# controller.net
KiCad netlist of a schematic drawn in EAGLE
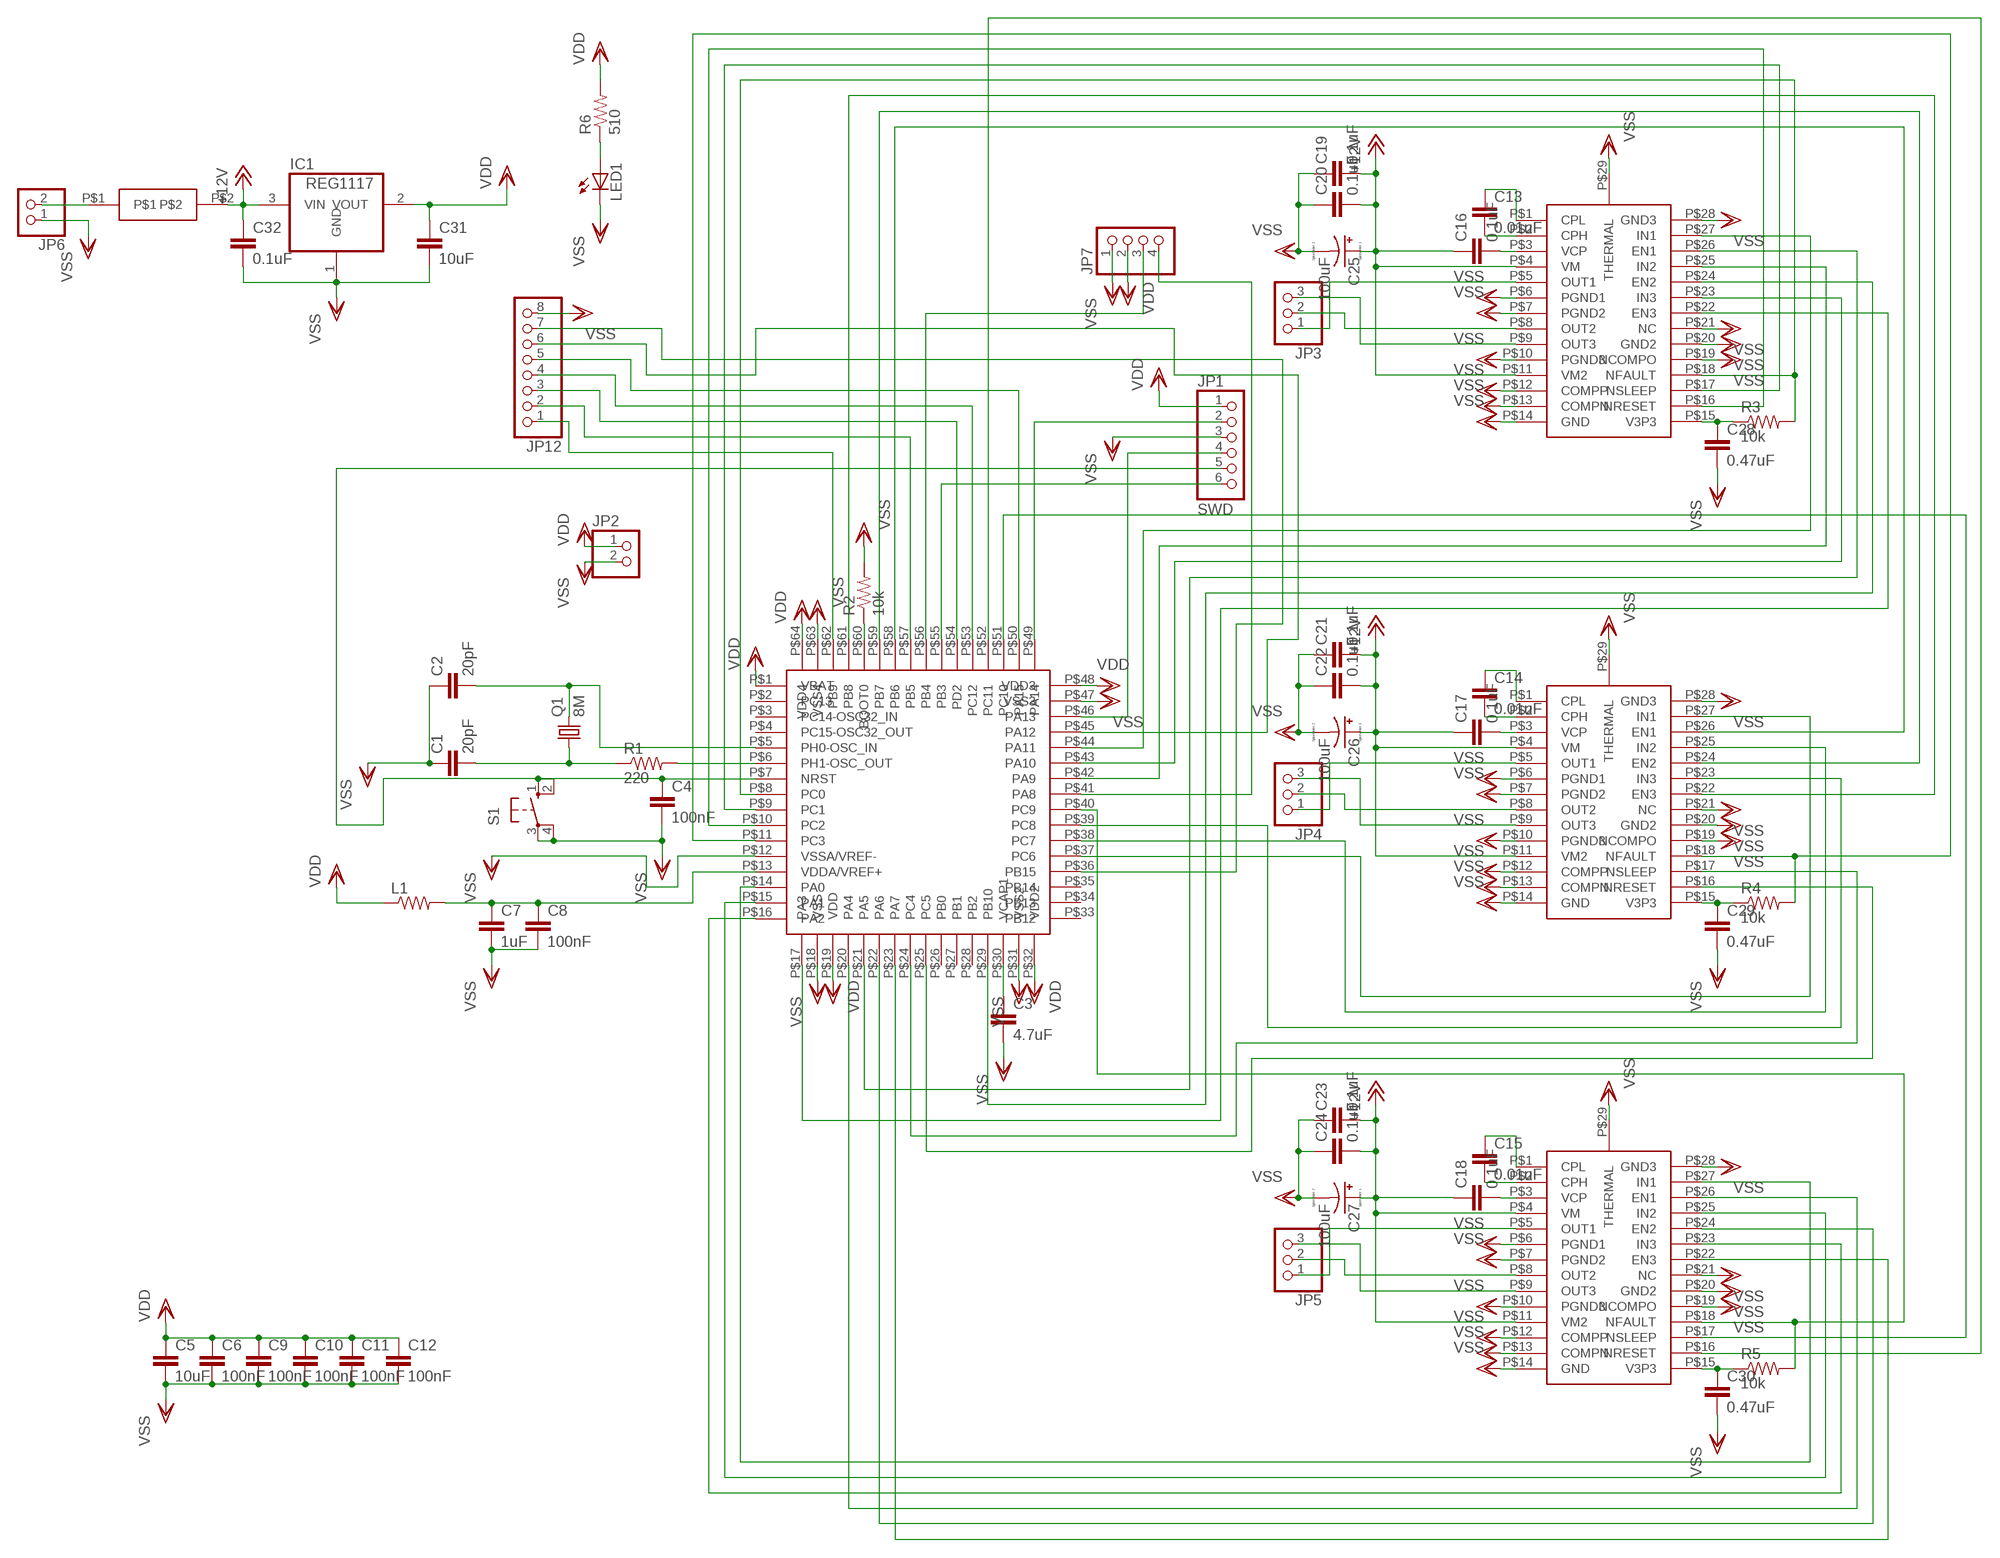
[diagram p0: schematic, sheet 1]

(export (version "E")
  (design (tool "Eeschema 10.0.6"))
  (components
    (comp (ref "C1")
      (value "20pF")
      (footprint "eagle-import:C0402")
      (libsource (lib "eagle-import") (part "C-EUC0402"))
    )
    (comp (ref "C2")
      (value "20pF")
      (footprint "eagle-import:C0402")
      (libsource (lib "eagle-import") (part "C-EUC0402"))
    )
    (comp (ref "C3")
      (value "4.7uF")
      (footprint "eagle-import:C1206")
      (libsource (lib "eagle-import") (part "C-EUC1206"))
    )
    (comp (ref "C4")
      (value "100nF")
      (footprint "eagle-import:C0402")
      (libsource (lib "eagle-import") (part "C-EUC0402"))
    )
    (comp (ref "C5")
      (value "10uF")
      (footprint "eagle-import:C1206")
      (libsource (lib "eagle-import") (part "C-EUC1206"))
    )
    (comp (ref "C6")
      (value "100nF")
      (footprint "eagle-import:C0402")
      (libsource (lib "eagle-import") (part "C-EUC0402"))
    )
    (comp (ref "C7")
      (value "1uF")
      (footprint "eagle-import:C0603")
      (libsource (lib "eagle-import") (part "C-EUC0603"))
    )
    (comp (ref "C8")
      (value "100nF")
      (footprint "eagle-import:C0402")
      (libsource (lib "eagle-import") (part "C-EUC0402"))
    )
    (comp (ref "C9")
      (value "100nF")
      (footprint "eagle-import:C0402")
      (libsource (lib "eagle-import") (part "C-EUC0402"))
    )
    (comp (ref "C10")
      (value "100nF")
      (footprint "eagle-import:C0402")
      (libsource (lib "eagle-import") (part "C-EUC0402"))
    )
    (comp (ref "C11")
      (value "100nF")
      (footprint "eagle-import:C0402")
      (libsource (lib "eagle-import") (part "C-EUC0402"))
    )
    (comp (ref "C12")
      (value "100nF")
      (footprint "eagle-import:C0402")
      (libsource (lib "eagle-import") (part "C-EUC0402"))
    )
    (comp (ref "C13")
      (value "0.01uF")
      (footprint "eagle-import:C0603")
      (libsource (lib "eagle-import") (part "C-EUC0603"))
    )
    (comp (ref "C14")
      (value "0.01uF")
      (footprint "eagle-import:C0603")
      (libsource (lib "eagle-import") (part "C-EUC0603"))
    )
    (comp (ref "C15")
      (value "0.01uF")
      (footprint "eagle-import:C0603")
      (libsource (lib "eagle-import") (part "C-EUC0603"))
    )
    (comp (ref "C16")
      (value "0.1uF")
      (footprint "eagle-import:C0603")
      (libsource (lib "eagle-import") (part "C-EUC0603"))
    )
    (comp (ref "C17")
      (value "0.1uF")
      (footprint "eagle-import:C0603")
      (libsource (lib "eagle-import") (part "C-EUC0603"))
    )
    (comp (ref "C18")
      (value "0.1uF")
      (footprint "eagle-import:C0603")
      (libsource (lib "eagle-import") (part "C-EUC0603"))
    )
    (comp (ref "C19")
      (value "0.1uF")
      (footprint "eagle-import:C0603")
      (libsource (lib "eagle-import") (part "C-EUC0603"))
    )
    (comp (ref "C20")
      (value "0.1uF")
      (footprint "eagle-import:C0603")
      (libsource (lib "eagle-import") (part "C-EUC0603"))
    )
    (comp (ref "C21")
      (value "0.1uF")
      (footprint "eagle-import:C0603")
      (libsource (lib "eagle-import") (part "C-EUC0603"))
    )
    (comp (ref "C22")
      (value "0.1uF")
      (footprint "eagle-import:C0603")
      (libsource (lib "eagle-import") (part "C-EUC0603"))
    )
    (comp (ref "C23")
      (value "0.1uF")
      (footprint "eagle-import:C0603")
      (libsource (lib "eagle-import") (part "C-EUC0603"))
    )
    (comp (ref "C24")
      (value "0.1uF")
      (footprint "eagle-import:C0603")
      (libsource (lib "eagle-import") (part "C-EUC0603"))
    )
    (comp (ref "C25")
      (value "100uF")
      (footprint "eagle-import:PANASONIC_D")
      (libsource (lib "eagle-import") (part "CPOL-USD"))
    )
    (comp (ref "C26")
      (value "100uF")
      (footprint "eagle-import:PANASONIC_D")
      (libsource (lib "eagle-import") (part "CPOL-USD"))
    )
    (comp (ref "C27")
      (value "100uF")
      (footprint "eagle-import:PANASONIC_D")
      (libsource (lib "eagle-import") (part "CPOL-USD"))
    )
    (comp (ref "C28")
      (value "0.47uF")
      (footprint "eagle-import:C0603")
      (libsource (lib "eagle-import") (part "C-EUC0603"))
    )
    (comp (ref "C29")
      (value "0.47uF")
      (footprint "eagle-import:C0603")
      (libsource (lib "eagle-import") (part "C-EUC0603"))
    )
    (comp (ref "C30")
      (value "0.47uF")
      (footprint "eagle-import:C0603")
      (libsource (lib "eagle-import") (part "C-EUC0603"))
    )
    (comp (ref "C31")
      (value "10uF")
      (footprint "eagle-import:C1206")
      (libsource (lib "eagle-import") (part "C-EUC1206"))
    )
    (comp (ref "C32")
      (value "0.1uF")
      (footprint "eagle-import:C1206")
      (libsource (lib "eagle-import") (part "C-EUC1206"))
    )
    (comp (ref "IC1")
      (value "REG1117")
      (footprint "eagle-import:SOT223")
      (libsource (lib "eagle-import") (part "REG1117"))
    )
    (comp (ref "JP1")
      (value "SWD")
      (footprint "eagle-import:1X06")
      (libsource (lib "eagle-import") (part "PINHD-1X6"))
    )
    (comp (ref "JP2")
      (value "PINHD-1X2")
      (footprint "eagle-import:1X02")
      (libsource (lib "eagle-import") (part "PINHD-1X2"))
    )
    (comp (ref "JP3")
      (value "PINHD-1X3")
      (footprint "eagle-import:1X03")
      (libsource (lib "eagle-import") (part "PINHD-1X3"))
    )
    (comp (ref "JP4")
      (value "PINHD-1X3")
      (footprint "eagle-import:1X03")
      (libsource (lib "eagle-import") (part "PINHD-1X3"))
    )
    (comp (ref "JP5")
      (value "PINHD-1X3")
      (footprint "eagle-import:1X03")
      (libsource (lib "eagle-import") (part "PINHD-1X3"))
    )
    (comp (ref "JP6")
      (value "PINHD-1X2")
      (footprint "eagle-import:1X02")
      (libsource (lib "eagle-import") (part "PINHD-1X2"))
    )
    (comp (ref "JP7")
      (value "PINHD-1X4")
      (footprint "eagle-import:1X04")
      (libsource (lib "eagle-import") (part "PINHD-1X4"))
    )
    (comp (ref "JP12")
      (value "PINHD-1X8")
      (footprint "eagle-import:1X08")
      (libsource (lib "eagle-import") (part "PINHD-1X8"))
    )
    (comp (ref "L1")
      (value "R-US_R0603")
      (footprint "eagle-import:R0603")
      (libsource (lib "eagle-import") (part "R-US_R0603"))
    )
    (comp (ref "LED1")
      (value "LEDCHIP-LED0603")
      (footprint "eagle-import:CHIP-LED0603")
      (libsource (lib "eagle-import") (part "LEDCHIP-LED0603"))
    )
    (comp (ref "Q1")
      (value "8M")
      (footprint "eagle-import:HC49_S")
      (libsource (lib "eagle-import") (part "CRYSTALHC49S"))
    )
    (comp (ref "R1")
      (value "220")
      (footprint "eagle-import:R0402")
      (libsource (lib "eagle-import") (part "R-US_R0402"))
    )
    (comp (ref "R2")
      (value "10k")
      (footprint "eagle-import:R0402")
      (libsource (lib "eagle-import") (part "R-US_R0402"))
    )
    (comp (ref "R3")
      (value "10k")
      (footprint "eagle-import:R0402")
      (libsource (lib "eagle-import") (part "R-US_R0402"))
    )
    (comp (ref "R4")
      (value "10k")
      (footprint "eagle-import:R0402")
      (libsource (lib "eagle-import") (part "R-US_R0402"))
    )
    (comp (ref "R5")
      (value "10k")
      (footprint "eagle-import:R0402")
      (libsource (lib "eagle-import") (part "R-US_R0402"))
    )
    (comp (ref "R6")
      (value "510")
      (footprint "eagle-import:R0402")
      (libsource (lib "eagle-import") (part "R-US_R0402"))
    )
    (comp (ref "S1")
      (value "10-XX")
      (footprint "eagle-import:B3F-10XX")
      (fields (field (name "MPN") "B3F-1000"))
      (libsource (lib "eagle-import") (part "10-XX"))
    )
    (comp (ref "U$1")
      (value "STM32F411VET6")
      (footprint "eagle-import:STM32F411VET6")
      (libsource (lib "eagle-import") (part "STM32F411VET6"))
    )
    (comp (ref "U$2")
      (value "DRV8313")
      (footprint "eagle-import:DRV8313")
      (libsource (lib "eagle-import") (part "DRV8313"))
    )
    (comp (ref "U$3")
      (value "DRV8313")
      (footprint "eagle-import:DRV8313")
      (libsource (lib "eagle-import") (part "DRV8313"))
    )
    (comp (ref "U$4")
      (value "DRV8313")
      (footprint "eagle-import:DRV8313")
      (libsource (lib "eagle-import") (part "DRV8313"))
    )
    (comp (ref "U$5")
      (value "SOD123")
      (footprint "eagle-import:SOD123")
      (libsource (lib "eagle-import") (part "SOD123"))
    )
  )
  (nets
    (net (code "1") (name "+12V") (class "Default")
      (node (ref "C16") (pin "1") (pinfunction "1_1") (pintype "passive"))
      (node (ref "C17") (pin "1") (pinfunction "1_1") (pintype "passive"))
      (node (ref "C18") (pin "1") (pinfunction "1_1") (pintype "passive"))
      (node (ref "C19") (pin "2") (pinfunction "2_2") (pintype "passive"))
      (node (ref "C20") (pin "2") (pinfunction "2_2") (pintype "passive"))
      (node (ref "C21") (pin "2") (pinfunction "2_2") (pintype "passive"))
      (node (ref "C22") (pin "2") (pinfunction "2_2") (pintype "passive"))
      (node (ref "C23") (pin "2") (pinfunction "2_2") (pintype "passive"))
      (node (ref "C24") (pin "2") (pinfunction "2_2") (pintype "passive"))
      (node (ref "C25") (pin "+") (pinfunction "+_+") (pintype "passive"))
      (node (ref "C26") (pin "+") (pinfunction "+_+") (pintype "passive"))
      (node (ref "C27") (pin "+") (pinfunction "+_+") (pintype "passive"))
      (node (ref "C32") (pin "1") (pinfunction "1_1") (pintype "passive"))
      (node (ref "IC1") (pin "3") (pinfunction "VIN_3") (pintype "input"))
      (node (ref "U$2") (pin "P$11") (pinfunction "VM2_P$11") (pintype "bidirectional"))
      (node (ref "U$2") (pin "P$4") (pinfunction "VM_P$4") (pintype "bidirectional"))
      (node (ref "U$3") (pin "P$11") (pinfunction "VM2_P$11") (pintype "bidirectional"))
      (node (ref "U$3") (pin "P$4") (pinfunction "VM_P$4") (pintype "bidirectional"))
      (node (ref "U$4") (pin "P$11") (pinfunction "VM2_P$11") (pintype "bidirectional"))
      (node (ref "U$4") (pin "P$4") (pinfunction "VM_P$4") (pintype "bidirectional"))
      (node (ref "U$5") (pin "P$2") (pinfunction "P$2_P$2") (pintype "bidirectional"))
    )
    (net (code "2") (name "Net-(C1-Pad2)") (class "Default")
      (node (ref "C1") (pin "2") (pinfunction "2_2") (pintype "passive"))
      (node (ref "Q1") (pin "1") (pinfunction "1_1") (pintype "passive"))
      (node (ref "R1") (pin "1") (pinfunction "1_1") (pintype "passive"))
    )
    (net (code "3") (name "Net-(JP6-Pad2)") (class "Default")
      (node (ref "JP6") (pin "2") (pinfunction "2_2") (pintype "passive"))
      (node (ref "U$5") (pin "P$1") (pinfunction "P$1_P$1") (pintype "bidirectional"))
    )
    (net (code "4") (name "Net-(LED1-PadA)") (class "Default")
      (node (ref "LED1") (pin "A") (pinfunction "A_A") (pintype "passive"))
      (node (ref "R6") (pin "1") (pinfunction "1_1") (pintype "passive"))
    )
    (net (code "5") (name "Net-(S1-S)") (class "Default")
      (node (ref "C4") (pin "1") (pinfunction "1_1") (pintype "passive"))
      (node (ref "JP1") (pin "5") (pinfunction "5_5") (pintype "passive"))
      (node (ref "S1") (pin "1") (pinfunction "S_1") (pintype "passive"))
      (node (ref "S1") (pin "2") (pinfunction "S1_2") (pintype "passive"))
      (node (ref "U$1") (pin "P$7") (pinfunction "NRST_P$7") (pintype "bidirectional"))
    )
    (net (code "6") (name "Net-(U$1-BOOT0)") (class "Default")
      (node (ref "R2") (pin "1") (pinfunction "1_1") (pintype "passive"))
      (node (ref "U$1") (pin "P$60") (pinfunction "BOOT0_P$60") (pintype "bidirectional"))
    )
    (net (code "7") (name "Net-(U$1-PA0)") (class "Default")
      (node (ref "U$1") (pin "P$14") (pinfunction "PA0_P$14") (pintype "bidirectional"))
      (node (ref "U$4") (pin "P$27") (pinfunction "IN1_P$27") (pintype "bidirectional"))
    )
    (net (code "8") (name "Net-(U$1-PA1)") (class "Default")
      (node (ref "U$1") (pin "P$15") (pinfunction "PA1_P$15") (pintype "bidirectional"))
      (node (ref "U$4") (pin "P$25") (pinfunction "IN2_P$25") (pintype "bidirectional"))
    )
    (net (code "9") (name "Net-(U$1-PA2)") (class "Default")
      (node (ref "U$1") (pin "P$16") (pinfunction "PA2_P$16") (pintype "bidirectional"))
      (node (ref "U$4") (pin "P$23") (pinfunction "IN3_P$23") (pintype "bidirectional"))
    )
    (net (code "10") (name "Net-(U$1-PA3)") (class "Default")
      (node (ref "U$1") (pin "P$17") (pinfunction "PA3_P$17") (pintype "bidirectional"))
      (node (ref "U$2") (pin "P$22") (pinfunction "EN3_P$22") (pintype "bidirectional"))
    )
    (net (code "11") (name "Net-(U$1-PA4)") (class "Default")
      (node (ref "U$1") (pin "P$20") (pinfunction "PA4_P$20") (pintype "bidirectional"))
      (node (ref "U$4") (pin "P$26") (pinfunction "EN1_P$26") (pintype "bidirectional"))
    )
    (net (code "12") (name "Net-(U$1-PA5)") (class "Default")
      (node (ref "U$1") (pin "P$21") (pinfunction "PA5_P$21") (pintype "bidirectional"))
      (node (ref "U$2") (pin "P$26") (pinfunction "EN1_P$26") (pintype "bidirectional"))
    )
    (net (code "13") (name "Net-(U$1-PA6)") (class "Default")
      (node (ref "U$1") (pin "P$22") (pinfunction "PA6_P$22") (pintype "bidirectional"))
      (node (ref "U$4") (pin "P$24") (pinfunction "EN2_P$24") (pintype "bidirectional"))
    )
    (net (code "14") (name "Net-(U$1-PA7)") (class "Default")
      (node (ref "U$1") (pin "P$23") (pinfunction "PA7_P$23") (pintype "bidirectional"))
      (node (ref "U$4") (pin "P$22") (pinfunction "EN3_P$22") (pintype "bidirectional"))
    )
    (net (code "15") (name "Net-(U$1-PA8)") (class "Default")
      (node (ref "JP7") (pin "4") (pinfunction "4_4") (pintype "passive"))
      (node (ref "U$1") (pin "P$41") (pinfunction "PA8_P$41") (pintype "bidirectional"))
    )
    (net (code "16") (name "Net-(U$1-PA9)") (class "Default")
      (node (ref "U$1") (pin "P$42") (pinfunction "PA9_P$42") (pintype "bidirectional"))
      (node (ref "U$2") (pin "P$25") (pinfunction "IN2_P$25") (pintype "bidirectional"))
    )
    (net (code "17") (name "Net-(U$1-PA10)") (class "Default")
      (node (ref "U$1") (pin "P$43") (pinfunction "PA10_P$43") (pintype "bidirectional"))
      (node (ref "U$2") (pin "P$23") (pinfunction "IN3_P$23") (pintype "bidirectional"))
    )
    (net (code "18") (name "Net-(U$1-PA11)") (class "Default")
      (node (ref "U$1") (pin "P$44") (pinfunction "PA11_P$44") (pintype "bidirectional"))
      (node (ref "U$2") (pin "P$27") (pinfunction "IN1_P$27") (pintype "bidirectional"))
    )
    (net (code "19") (name "Net-(U$1-PA12)") (class "Default")
      (node (ref "JP12") (pin "6") (pinfunction "6_6") (pintype "passive"))
      (node (ref "U$1") (pin "P$45") (pinfunction "PA12_P$45") (pintype "bidirectional"))
    )
    (net (code "20") (name "Net-(U$1-PA13)") (class "Default")
      (node (ref "JP1") (pin "4") (pinfunction "4_4") (pintype "passive"))
      (node (ref "U$1") (pin "P$46") (pinfunction "PA13_P$46") (pintype "bidirectional"))
    )
    (net (code "21") (name "Net-(U$1-PA14)") (class "Default")
      (node (ref "JP1") (pin "2") (pinfunction "2_2") (pintype "passive"))
      (node (ref "U$1") (pin "P$49") (pinfunction "PA14_P$49") (pintype "bidirectional"))
    )
    (net (code "22") (name "Net-(U$1-PA15)") (class "Default")
      (node (ref "JP12") (pin "5") (pinfunction "5_5") (pintype "passive"))
      (node (ref "U$1") (pin "P$50") (pinfunction "PA15_P$50") (pintype "bidirectional"))
    )
    (net (code "23") (name "Net-(U$1-PB3)") (class "Default")
      (node (ref "JP1") (pin "6") (pinfunction "6_6") (pintype "passive"))
      (node (ref "U$1") (pin "P$55") (pinfunction "PB3_P$55") (pintype "bidirectional"))
    )
    (net (code "24") (name "Net-(U$1-PB4)") (class "Default")
      (node (ref "JP7") (pin "3") (pinfunction "3_3") (pintype "passive"))
      (node (ref "U$1") (pin "P$56") (pinfunction "PB4_P$56") (pintype "bidirectional"))
    )
    (net (code "25") (name "Net-(U$1-PB5)") (class "Default")
      (node (ref "JP12") (pin "2") (pinfunction "2_2") (pintype "passive"))
      (node (ref "U$1") (pin "P$57") (pinfunction "PB5_P$57") (pintype "bidirectional"))
    )
    (net (code "26") (name "Net-(U$1-PB6)") (class "Default")
      (node (ref "U$1") (pin "P$58") (pinfunction "PB6_P$58") (pintype "bidirectional"))
      (node (ref "U$3") (pin "P$26") (pinfunction "EN1_P$26") (pintype "bidirectional"))
    )
    (net (code "27") (name "Net-(U$1-PB7)") (class "Default")
      (node (ref "U$1") (pin "P$59") (pinfunction "PB7_P$59") (pintype "bidirectional"))
      (node (ref "U$3") (pin "P$24") (pinfunction "EN2_P$24") (pintype "bidirectional"))
    )
    (net (code "28") (name "Net-(U$1-PB8)") (class "Default")
      (node (ref "U$1") (pin "P$61") (pinfunction "PB8_P$61") (pintype "bidirectional"))
      (node (ref "U$3") (pin "P$22") (pinfunction "EN3_P$22") (pintype "bidirectional"))
    )
    (net (code "29") (name "Net-(U$1-PB9)") (class "Default")
      (node (ref "JP12") (pin "1") (pinfunction "1_1") (pintype "passive"))
      (node (ref "U$1") (pin "P$62") (pinfunction "PB9_P$62") (pintype "bidirectional"))
    )
    (net (code "30") (name "Net-(U$1-PB10)") (class "Default")
      (node (ref "U$1") (pin "P$29") (pinfunction "PB10_P$29") (pintype "bidirectional"))
      (node (ref "U$2") (pin "P$24") (pinfunction "EN2_P$24") (pintype "bidirectional"))
    )
    (net (code "31") (name "Net-(U$1-PB15)") (class "Default")
      (node (ref "JP12") (pin "7") (pinfunction "7_7") (pintype "passive"))
      (node (ref "U$1") (pin "P$36") (pinfunction "PB15_P$36") (pintype "bidirectional"))
    )
    (net (code "32") (name "Net-(U$1-PC0)") (class "Default")
      (node (ref "R3") (pin "2") (pinfunction "2_2") (pintype "passive"))
      (node (ref "U$1") (pin "P$8") (pinfunction "PC0_P$8") (pintype "bidirectional"))
      (node (ref "U$2") (pin "P$18") (pinfunction "NFAULT_P$18") (pintype "bidirectional"))
    )
    (net (code "33") (name "Net-(U$1-PC1)") (class "Default")
      (node (ref "U$1") (pin "P$9") (pinfunction "PC1_P$9") (pintype "bidirectional"))
      (node (ref "U$2") (pin "P$17") (pinfunction "NSLEEP_P$17") (pintype "bidirectional"))
    )
    (net (code "34") (name "Net-(U$1-PC2)") (class "Default")
      (node (ref "U$1") (pin "P$10") (pinfunction "PC2_P$10") (pintype "bidirectional"))
      (node (ref "U$2") (pin "P$16") (pinfunction "NRESET_P$16") (pintype "bidirectional"))
    )
    (net (code "35") (name "Net-(U$1-PC3)") (class "Default")
      (node (ref "R4") (pin "2") (pinfunction "2_2") (pintype "passive"))
      (node (ref "U$1") (pin "P$11") (pinfunction "PC3_P$11") (pintype "bidirectional"))
      (node (ref "U$3") (pin "P$18") (pinfunction "NFAULT_P$18") (pintype "bidirectional"))
    )
    (net (code "36") (name "Net-(U$1-PC4)") (class "Default")
      (node (ref "U$1") (pin "P$24") (pinfunction "PC4_P$24") (pintype "bidirectional"))
      (node (ref "U$3") (pin "P$17") (pinfunction "NSLEEP_P$17") (pintype "bidirectional"))
    )
    (net (code "37") (name "Net-(U$1-PC5)") (class "Default")
      (node (ref "U$1") (pin "P$25") (pinfunction "PC5_P$25") (pintype "bidirectional"))
      (node (ref "U$3") (pin "P$16") (pinfunction "NRESET_P$16") (pintype "bidirectional"))
    )
    (net (code "38") (name "Net-(U$1-PC6)") (class "Default")
      (node (ref "U$1") (pin "P$37") (pinfunction "PC6_P$37") (pintype "bidirectional"))
      (node (ref "U$3") (pin "P$27") (pinfunction "IN1_P$27") (pintype "bidirectional"))
    )
    (net (code "39") (name "Net-(U$1-PC7)") (class "Default")
      (node (ref "U$1") (pin "P$38") (pinfunction "PC7_P$38") (pintype "bidirectional"))
      (node (ref "U$3") (pin "P$25") (pinfunction "IN2_P$25") (pintype "bidirectional"))
    )
    (net (code "40") (name "Net-(U$1-PC8)") (class "Default")
      (node (ref "U$1") (pin "P$39") (pinfunction "PC8_P$39") (pintype "bidirectional"))
      (node (ref "U$3") (pin "P$23") (pinfunction "IN3_P$23") (pintype "bidirectional"))
    )
    (net (code "41") (name "Net-(U$1-PC9)") (class "Default")
      (node (ref "R5") (pin "2") (pinfunction "2_2") (pintype "passive"))
      (node (ref "U$1") (pin "P$40") (pinfunction "PC9_P$40") (pintype "bidirectional"))
      (node (ref "U$4") (pin "P$18") (pinfunction "NFAULT_P$18") (pintype "bidirectional"))
    )
    (net (code "42") (name "Net-(U$1-PC10)") (class "Default")
      (node (ref "U$1") (pin "P$51") (pinfunction "PC10_P$51") (pintype "bidirectional"))
      (node (ref "U$4") (pin "P$17") (pinfunction "NSLEEP_P$17") (pintype "bidirectional"))
    )
    (net (code "43") (name "Net-(U$1-PC11)") (class "Default")
      (node (ref "U$1") (pin "P$52") (pinfunction "PC11_P$52") (pintype "bidirectional"))
      (node (ref "U$4") (pin "P$16") (pinfunction "NRESET_P$16") (pintype "bidirectional"))
    )
    (net (code "44") (name "Net-(U$1-PC12)") (class "Default")
      (node (ref "JP12") (pin "4") (pinfunction "4_4") (pintype "passive"))
      (node (ref "U$1") (pin "P$53") (pinfunction "PC12_P$53") (pintype "bidirectional"))
    )
    (net (code "45") (name "Net-(U$1-PD2)") (class "Default")
      (node (ref "JP12") (pin "3") (pinfunction "3_3") (pintype "passive"))
      (node (ref "U$1") (pin "P$54") (pinfunction "PD2_P$54") (pintype "bidirectional"))
    )
    (net (code "46") (name "Net-(U$1-PH0-OSC_IN)") (class "Default")
      (node (ref "C2") (pin "2") (pinfunction "2_2") (pintype "passive"))
      (node (ref "Q1") (pin "2") (pinfunction "2_2") (pintype "passive"))
      (node (ref "U$1") (pin "P$5") (pinfunction "PH0-OSC_IN_P$5") (pintype "bidirectional"))
    )
    (net (code "47") (name "Net-(U$1-PH1-OSC_OUT)") (class "Default")
      (node (ref "R1") (pin "2") (pinfunction "2_2") (pintype "passive"))
      (node (ref "U$1") (pin "P$6") (pinfunction "PH1-OSC_OUT_P$6") (pintype "bidirectional"))
    )
    (net (code "48") (name "Net-(U$1-VCAP1)") (class "Default")
      (node (ref "C3") (pin "1") (pinfunction "1_1") (pintype "passive"))
      (node (ref "U$1") (pin "P$30") (pinfunction "VCAP1_P$30") (pintype "bidirectional"))
    )
    (net (code "49") (name "Net-(U$1-VDDA{slash}VREF+)") (class "Default")
      (node (ref "C7") (pin "1") (pinfunction "1_1") (pintype "passive"))
      (node (ref "C8") (pin "1") (pinfunction "1_1") (pintype "passive"))
      (node (ref "L1") (pin "2") (pinfunction "2_2") (pintype "passive"))
      (node (ref "U$1") (pin "P$13") (pinfunction "VDDA/VREF+_P$13") (pintype "bidirectional"))
    )
    (net (code "50") (name "Net-(U$2-CPH)") (class "Default")
      (node (ref "C13") (pin "2") (pinfunction "2_2") (pintype "passive"))
      (node (ref "U$2") (pin "P$2") (pinfunction "CPH_P$2") (pintype "bidirectional"))
    )
    (net (code "51") (name "Net-(U$2-CPL)") (class "Default")
      (node (ref "C13") (pin "1") (pinfunction "1_1") (pintype "passive"))
      (node (ref "U$2") (pin "P$1") (pinfunction "CPL_P$1") (pintype "bidirectional"))
    )
    (net (code "52") (name "Net-(U$2-OUT1)") (class "Default")
      (node (ref "JP3") (pin "1") (pinfunction "1_1") (pintype "passive"))
      (node (ref "U$2") (pin "P$5") (pinfunction "OUT1_P$5") (pintype "bidirectional"))
    )
    (net (code "53") (name "Net-(U$2-OUT2)") (class "Default")
      (node (ref "JP3") (pin "2") (pinfunction "2_2") (pintype "passive"))
      (node (ref "U$2") (pin "P$8") (pinfunction "OUT2_P$8") (pintype "bidirectional"))
    )
    (net (code "54") (name "Net-(U$2-OUT3)") (class "Default")
      (node (ref "JP3") (pin "3") (pinfunction "3_3") (pintype "passive"))
      (node (ref "U$2") (pin "P$9") (pinfunction "OUT3_P$9") (pintype "bidirectional"))
    )
    (net (code "55") (name "Net-(U$2-V3P3)") (class "Default")
      (node (ref "C28") (pin "1") (pinfunction "1_1") (pintype "passive"))
      (node (ref "R3") (pin "1") (pinfunction "1_1") (pintype "passive"))
      (node (ref "U$2") (pin "P$15") (pinfunction "V3P3_P$15") (pintype "bidirectional"))
    )
    (net (code "56") (name "Net-(U$2-VCP)") (class "Default")
      (node (ref "C16") (pin "2") (pinfunction "2_2") (pintype "passive"))
      (node (ref "U$2") (pin "P$3") (pinfunction "VCP_P$3") (pintype "bidirectional"))
    )
    (net (code "57") (name "Net-(U$3-CPH)") (class "Default")
      (node (ref "C14") (pin "2") (pinfunction "2_2") (pintype "passive"))
      (node (ref "U$3") (pin "P$2") (pinfunction "CPH_P$2") (pintype "bidirectional"))
    )
    (net (code "58") (name "Net-(U$3-CPL)") (class "Default")
      (node (ref "C14") (pin "1") (pinfunction "1_1") (pintype "passive"))
      (node (ref "U$3") (pin "P$1") (pinfunction "CPL_P$1") (pintype "bidirectional"))
    )
    (net (code "59") (name "Net-(U$3-OUT1)") (class "Default")
      (node (ref "JP4") (pin "1") (pinfunction "1_1") (pintype "passive"))
      (node (ref "U$3") (pin "P$5") (pinfunction "OUT1_P$5") (pintype "bidirectional"))
    )
    (net (code "60") (name "Net-(U$3-OUT2)") (class "Default")
      (node (ref "JP4") (pin "2") (pinfunction "2_2") (pintype "passive"))
      (node (ref "U$3") (pin "P$8") (pinfunction "OUT2_P$8") (pintype "bidirectional"))
    )
    (net (code "61") (name "Net-(U$3-OUT3)") (class "Default")
      (node (ref "JP4") (pin "3") (pinfunction "3_3") (pintype "passive"))
      (node (ref "U$3") (pin "P$9") (pinfunction "OUT3_P$9") (pintype "bidirectional"))
    )
    (net (code "62") (name "Net-(U$3-V3P3)") (class "Default")
      (node (ref "C29") (pin "1") (pinfunction "1_1") (pintype "passive"))
      (node (ref "R4") (pin "1") (pinfunction "1_1") (pintype "passive"))
      (node (ref "U$3") (pin "P$15") (pinfunction "V3P3_P$15") (pintype "bidirectional"))
    )
    (net (code "63") (name "Net-(U$3-VCP)") (class "Default")
      (node (ref "C17") (pin "2") (pinfunction "2_2") (pintype "passive"))
      (node (ref "U$3") (pin "P$3") (pinfunction "VCP_P$3") (pintype "bidirectional"))
    )
    (net (code "64") (name "Net-(U$4-CPH)") (class "Default")
      (node (ref "C15") (pin "2") (pinfunction "2_2") (pintype "passive"))
      (node (ref "U$4") (pin "P$2") (pinfunction "CPH_P$2") (pintype "bidirectional"))
    )
    (net (code "65") (name "Net-(U$4-CPL)") (class "Default")
      (node (ref "C15") (pin "1") (pinfunction "1_1") (pintype "passive"))
      (node (ref "U$4") (pin "P$1") (pinfunction "CPL_P$1") (pintype "bidirectional"))
    )
    (net (code "66") (name "Net-(U$4-OUT1)") (class "Default")
      (node (ref "JP5") (pin "1") (pinfunction "1_1") (pintype "passive"))
      (node (ref "U$4") (pin "P$5") (pinfunction "OUT1_P$5") (pintype "bidirectional"))
    )
    (net (code "67") (name "Net-(U$4-OUT2)") (class "Default")
      (node (ref "JP5") (pin "2") (pinfunction "2_2") (pintype "passive"))
      (node (ref "U$4") (pin "P$8") (pinfunction "OUT2_P$8") (pintype "bidirectional"))
    )
    (net (code "68") (name "Net-(U$4-OUT3)") (class "Default")
      (node (ref "JP5") (pin "3") (pinfunction "3_3") (pintype "passive"))
      (node (ref "U$4") (pin "P$9") (pinfunction "OUT3_P$9") (pintype "bidirectional"))
    )
    (net (code "69") (name "Net-(U$4-V3P3)") (class "Default")
      (node (ref "C30") (pin "1") (pinfunction "1_1") (pintype "passive"))
      (node (ref "R5") (pin "1") (pinfunction "1_1") (pintype "passive"))
      (node (ref "U$4") (pin "P$15") (pinfunction "V3P3_P$15") (pintype "bidirectional"))
    )
    (net (code "70") (name "Net-(U$4-VCP)") (class "Default")
      (node (ref "C18") (pin "2") (pinfunction "2_2") (pintype "passive"))
      (node (ref "U$4") (pin "P$3") (pinfunction "VCP_P$3") (pintype "bidirectional"))
    )
    (net (code "71") (name "VDD") (class "Default")
      (node (ref "C10") (pin "1") (pinfunction "1_1") (pintype "passive"))
      (node (ref "C11") (pin "1") (pinfunction "1_1") (pintype "passive"))
      (node (ref "C12") (pin "1") (pinfunction "1_1") (pintype "passive"))
      (node (ref "C31") (pin "1") (pinfunction "1_1") (pintype "passive"))
      (node (ref "C5") (pin "1") (pinfunction "1_1") (pintype "passive"))
      (node (ref "C6") (pin "1") (pinfunction "1_1") (pintype "passive"))
      (node (ref "C9") (pin "1") (pinfunction "1_1") (pintype "passive"))
      (node (ref "IC1") (pin "2") (pinfunction "VOUT_2") (pintype "power_in"))
      (node (ref "JP1") (pin "1") (pinfunction "1_1") (pintype "passive"))
      (node (ref "JP2") (pin "1") (pinfunction "1_1") (pintype "passive"))
      (node (ref "JP7") (pin "2") (pinfunction "2_2") (pintype "passive"))
      (node (ref "L1") (pin "1") (pinfunction "1_1") (pintype "passive"))
      (node (ref "R6") (pin "2") (pinfunction "2_2") (pintype "passive"))
      (node (ref "U$1") (pin "P$1") (pinfunction "VBAT_P$1") (pintype "bidirectional"))
      (node (ref "U$1") (pin "P$19") (pinfunction "VDD_P$19") (pintype "bidirectional"))
      (node (ref "U$1") (pin "P$32") (pinfunction "VDD2_P$32") (pintype "bidirectional"))
      (node (ref "U$1") (pin "P$48") (pinfunction "VDD3_P$48") (pintype "bidirectional"))
      (node (ref "U$1") (pin "P$64") (pinfunction "VDD4_P$64") (pintype "bidirectional"))
    )
    (net (code "72") (name "VSS") (class "Default")
      (node (ref "C1") (pin "1") (pinfunction "1_1") (pintype "passive"))
      (node (ref "C10") (pin "2") (pinfunction "2_2") (pintype "passive"))
      (node (ref "C11") (pin "2") (pinfunction "2_2") (pintype "passive"))
      (node (ref "C12") (pin "2") (pinfunction "2_2") (pintype "passive"))
      (node (ref "C19") (pin "1") (pinfunction "1_1") (pintype "passive"))
      (node (ref "C2") (pin "1") (pinfunction "1_1") (pintype "passive"))
      (node (ref "C20") (pin "1") (pinfunction "1_1") (pintype "passive"))
      (node (ref "C21") (pin "1") (pinfunction "1_1") (pintype "passive"))
      (node (ref "C22") (pin "1") (pinfunction "1_1") (pintype "passive"))
      (node (ref "C23") (pin "1") (pinfunction "1_1") (pintype "passive"))
      (node (ref "C24") (pin "1") (pinfunction "1_1") (pintype "passive"))
      (node (ref "C25") (pin "-") (pinfunction "-_-") (pintype "passive"))
      (node (ref "C26") (pin "-") (pinfunction "-_-") (pintype "passive"))
      (node (ref "C27") (pin "-") (pinfunction "-_-") (pintype "passive"))
      (node (ref "C28") (pin "2") (pinfunction "2_2") (pintype "passive"))
      (node (ref "C29") (pin "2") (pinfunction "2_2") (pintype "passive"))
      (node (ref "C3") (pin "2") (pinfunction "2_2") (pintype "passive"))
      (node (ref "C30") (pin "2") (pinfunction "2_2") (pintype "passive"))
      (node (ref "C31") (pin "2") (pinfunction "2_2") (pintype "passive"))
      (node (ref "C32") (pin "2") (pinfunction "2_2") (pintype "passive"))
      (node (ref "C4") (pin "2") (pinfunction "2_2") (pintype "passive"))
      (node (ref "C5") (pin "2") (pinfunction "2_2") (pintype "passive"))
      (node (ref "C6") (pin "2") (pinfunction "2_2") (pintype "passive"))
      (node (ref "C7") (pin "2") (pinfunction "2_2") (pintype "passive"))
      (node (ref "C8") (pin "2") (pinfunction "2_2") (pintype "passive"))
      (node (ref "C9") (pin "2") (pinfunction "2_2") (pintype "passive"))
      (node (ref "IC1") (pin "1") (pinfunction "GND_1") (pintype "power_in"))
      (node (ref "JP1") (pin "3") (pinfunction "3_3") (pintype "passive"))
      (node (ref "JP12") (pin "8") (pinfunction "8_8") (pintype "passive"))
      (node (ref "JP2") (pin "2") (pinfunction "2_2") (pintype "passive"))
      (node (ref "JP6") (pin "1") (pinfunction "1_1") (pintype "passive"))
      (node (ref "JP7") (pin "1") (pinfunction "1_1") (pintype "passive"))
      (node (ref "LED1") (pin "C") (pinfunction "C_C") (pintype "passive"))
      (node (ref "R2") (pin "2") (pinfunction "2_2") (pintype "passive"))
      (node (ref "S1") (pin "3") (pinfunction "P_3") (pintype "passive"))
      (node (ref "S1") (pin "4") (pinfunction "P1_4") (pintype "passive"))
      (node (ref "U$1") (pin "P$12") (pinfunction "VSSA/VREF-_P$12") (pintype "bidirectional"))
      (node (ref "U$1") (pin "P$18") (pinfunction "VSS_P$18") (pintype "bidirectional"))
      (node (ref "U$1") (pin "P$31") (pinfunction "VSS2_P$31") (pintype "bidirectional"))
      (node (ref "U$1") (pin "P$47") (pinfunction "VSS3_P$47") (pintype "bidirectional"))
      (node (ref "U$1") (pin "P$63") (pinfunction "VSS4_P$63") (pintype "bidirectional"))
      (node (ref "U$2") (pin "P$10") (pinfunction "PGND3_P$10") (pintype "bidirectional"))
      (node (ref "U$2") (pin "P$12") (pinfunction "COMPP_P$12") (pintype "bidirectional"))
      (node (ref "U$2") (pin "P$13") (pinfunction "COMPN_P$13") (pintype "bidirectional"))
      (node (ref "U$2") (pin "P$14") (pinfunction "GND_P$14") (pintype "bidirectional"))
      (node (ref "U$2") (pin "P$19") (pinfunction "NCOMPO_P$19") (pintype "bidirectional"))
      (node (ref "U$2") (pin "P$20") (pinfunction "GND2_P$20") (pintype "bidirectional"))
      (node (ref "U$2") (pin "P$21") (pinfunction "NC_P$21") (pintype "bidirectional"))
      (node (ref "U$2") (pin "P$28") (pinfunction "GND3_P$28") (pintype "bidirectional"))
      (node (ref "U$2") (pin "P$29") (pinfunction "THERMAL_P$29") (pintype "bidirectional"))
      (node (ref "U$2") (pin "P$6") (pinfunction "PGND1_P$6") (pintype "bidirectional"))
      (node (ref "U$2") (pin "P$7") (pinfunction "PGND2_P$7") (pintype "bidirectional"))
      (node (ref "U$3") (pin "P$10") (pinfunction "PGND3_P$10") (pintype "bidirectional"))
      (node (ref "U$3") (pin "P$12") (pinfunction "COMPP_P$12") (pintype "bidirectional"))
      (node (ref "U$3") (pin "P$13") (pinfunction "COMPN_P$13") (pintype "bidirectional"))
      (node (ref "U$3") (pin "P$14") (pinfunction "GND_P$14") (pintype "bidirectional"))
      (node (ref "U$3") (pin "P$19") (pinfunction "NCOMPO_P$19") (pintype "bidirectional"))
      (node (ref "U$3") (pin "P$20") (pinfunction "GND2_P$20") (pintype "bidirectional"))
      (node (ref "U$3") (pin "P$21") (pinfunction "NC_P$21") (pintype "bidirectional"))
      (node (ref "U$3") (pin "P$28") (pinfunction "GND3_P$28") (pintype "bidirectional"))
      (node (ref "U$3") (pin "P$29") (pinfunction "THERMAL_P$29") (pintype "bidirectional"))
      (node (ref "U$3") (pin "P$6") (pinfunction "PGND1_P$6") (pintype "bidirectional"))
      (node (ref "U$3") (pin "P$7") (pinfunction "PGND2_P$7") (pintype "bidirectional"))
      (node (ref "U$4") (pin "P$10") (pinfunction "PGND3_P$10") (pintype "bidirectional"))
      (node (ref "U$4") (pin "P$12") (pinfunction "COMPP_P$12") (pintype "bidirectional"))
      (node (ref "U$4") (pin "P$13") (pinfunction "COMPN_P$13") (pintype "bidirectional"))
      (node (ref "U$4") (pin "P$14") (pinfunction "GND_P$14") (pintype "bidirectional"))
      (node (ref "U$4") (pin "P$19") (pinfunction "NCOMPO_P$19") (pintype "bidirectional"))
      (node (ref "U$4") (pin "P$20") (pinfunction "GND2_P$20") (pintype "bidirectional"))
      (node (ref "U$4") (pin "P$21") (pinfunction "NC_P$21") (pintype "bidirectional"))
      (node (ref "U$4") (pin "P$28") (pinfunction "GND3_P$28") (pintype "bidirectional"))
      (node (ref "U$4") (pin "P$29") (pinfunction "THERMAL_P$29") (pintype "bidirectional"))
      (node (ref "U$4") (pin "P$6") (pinfunction "PGND1_P$6") (pintype "bidirectional"))
      (node (ref "U$4") (pin "P$7") (pinfunction "PGND2_P$7") (pintype "bidirectional"))
    )
    (net (code "73") (name "unconnected-(U$1-PB0-PadP$26)") (class "Default")
      (node (ref "U$1") (pin "P$26") (pinfunction "PB0_P$26") (pintype "bidirectional"))
    )
    (net (code "74") (name "unconnected-(U$1-PB1-PadP$27)") (class "Default")
      (node (ref "U$1") (pin "P$27") (pinfunction "PB1_P$27") (pintype "bidirectional"))
    )
    (net (code "75") (name "unconnected-(U$1-PB2-PadP$28)") (class "Default")
      (node (ref "U$1") (pin "P$28") (pinfunction "PB2_P$28") (pintype "bidirectional"))
    )
    (net (code "76") (name "unconnected-(U$1-PB12-PadP$33)") (class "Default")
      (node (ref "U$1") (pin "P$33") (pinfunction "PB12_P$33") (pintype "bidirectional"))
    )
    (net (code "77") (name "unconnected-(U$1-PB13-PadP$34)") (class "Default")
      (node (ref "U$1") (pin "P$34") (pinfunction "PB13_P$34") (pintype "bidirectional"))
    )
    (net (code "78") (name "unconnected-(U$1-PB14-PadP$35)") (class "Default")
      (node (ref "U$1") (pin "P$35") (pinfunction "PB14_P$35") (pintype "bidirectional"))
    )
    (net (code "79") (name "unconnected-(U$1-PC13-PadP$2)") (class "Default")
      (node (ref "U$1") (pin "P$2") (pinfunction "PC13_P$2") (pintype "bidirectional"))
    )
    (net (code "80") (name "unconnected-(U$1-PC14-OSC32_IN-PadP$3)") (class "Default")
      (node (ref "U$1") (pin "P$3") (pinfunction "PC14-OSC32_IN_P$3") (pintype "bidirectional"))
    )
    (net (code "81") (name "unconnected-(U$1-PC15-OSC32_OUT-PadP$4)") (class "Default")
      (node (ref "U$1") (pin "P$4") (pinfunction "PC15-OSC32_OUT_P$4") (pintype "bidirectional"))
    )
  )
)
